# Controller.net
KiCad netlist of a schematic drawn in Altium Designer
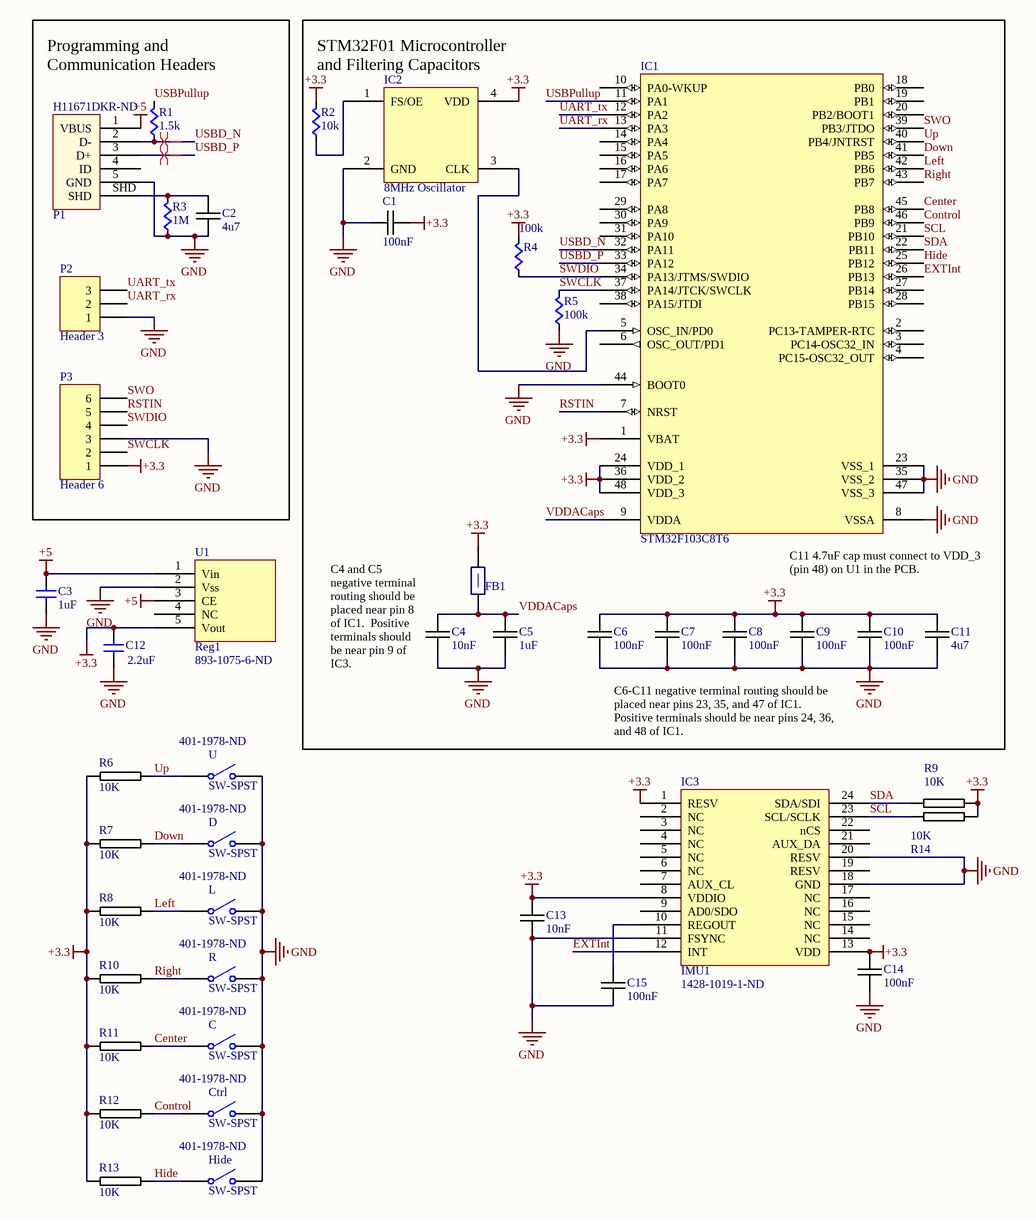
[diagram p0: Controller.SchDoc]

(export (version "E")
  (design (tool "Eeschema 10.0.6"))
  (components
    (comp (ref "C")
      (value "SW-SPST")
      (footprint "SPST C&K D6 Switch")
      (description "Single-Pole, Single-Throw Switch")
      (fields
        (field (name "SUPPLIER PART NUMBER 1") "401-1978-ND")
        (field (name "PUBLISHER") "Altium Limited")
      )
      (libsource (lib "Miscellaneous Devices") (part "SW-SPST"))
    )
    (comp (ref "C1")
      (value "100nF")
      (footprint "0603C-GENERIC")
      (description "CAP CER .10UF 25V X7R 10% 0603")
      (fields (field (name "MANUFACTURER") "TDK Corporation"))
      (libsource (lib "vh_altium_library") (part "0603C-100NF-25V-X7R-TDK"))
    )
    (comp (ref "C2")
      (value "4u7")
      (footprint "0603C-GENERIC")
      (description "CAPACITOR 0603 CERAMIC")
      (fields
        (field (name "MANUFACTURER PART NUMBER") "C1608X5R1A475K")
        (field (name "MANUFACTURER") "TDK Corporation")
      )
      (libsource (lib "vh_altium_library") (part "0603C-4U7-10V-X5R-TDK"))
    )
    (comp (ref "C3")
      (value "1uF")
      (footprint "CAPC0603")
      (fields (field (name "Comment") "Cap"))
      (libsource (lib "Passives") (part "Cap"))
    )
    (comp (ref "C4")
      (value "10nF")
      (footprint "0603C-GENERIC")
      (description "CAPACITOR 0603 CERAMIC")
      (fields
        (field (name "MANUFACTURER PART NUMBER") "GRM188R71H103KA01D")
        (field (name "MANUFACTURER") "Murata Electronics North America")
      )
      (libsource (lib "vh_altium_library") (part "0603C-10NF-50V-X7R-MUR"))
    )
    (comp (ref "C5")
      (value "1uF")
      (footprint "0603C-GENERIC")
      (description "CAPACITOR 0603 CERAMIC")
      (libsource (lib "vh_altium_library") (part "0603C-1UF-25V-X5R-SAM"))
    )
    (comp (ref "C6")
      (value "100nF")
      (footprint "0603C-GENERIC")
      (description "CAP CER 10000PF 50V X7R 10% 0603")
      (fields (field (name "TOLERANCE") "±10%"))
      (libsource (lib "vh_altium_library") (part "0603C-100NF-50V-X7R-TDK"))
    )
    (comp (ref "C7")
      (value "100nF")
      (footprint "0603C-GENERIC")
      (description "CAP CER 10000PF 50V X7R 10% 0603")
      (fields (field (name "TOLERANCE") "±10%"))
      (libsource (lib "vh_altium_library") (part "0603C-100NF-50V-X7R-TDK"))
    )
    (comp (ref "C8")
      (value "100nF")
      (footprint "0603C-GENERIC")
      (description "CAP CER 10000PF 50V X7R 10% 0603")
      (fields (field (name "TOLERANCE") "±10%"))
      (libsource (lib "vh_altium_library") (part "0603C-100NF-50V-X7R-TDK"))
    )
    (comp (ref "C9")
      (value "100nF")
      (footprint "0603C-GENERIC")
      (description "CAP CER 10000PF 50V X7R 10% 0603")
      (fields (field (name "TOLERANCE") "±10%"))
      (libsource (lib "vh_altium_library") (part "0603C-100NF-50V-X7R-TDK"))
    )
    (comp (ref "C10")
      (value "100nF")
      (footprint "0603C-GENERIC")
      (description "CAP CER 10000PF 50V X7R 10% 0603")
      (fields (field (name "TOLERANCE") "±10%"))
      (libsource (lib "vh_altium_library") (part "0603C-100NF-50V-X7R-TDK"))
    )
    (comp (ref "C11")
      (value "4u7")
      (footprint "0603C-GENERIC")
      (description "CAPACITOR 0603 CERAMIC")
      (fields
        (field (name "MANUFACTURER PART NUMBER") "C1608X5R1A475K")
        (field (name "MANUFACTURER") "TDK Corporation")
      )
      (libsource (lib "vh_altium_library") (part "0603C-4U7-10V-X5R-TDK"))
    )
    (comp (ref "C12")
      (value "2.2uF")
      (footprint "CAPC0603")
      (fields (field (name "Comment") "Cap"))
      (libsource (lib "Passives") (part "Cap"))
    )
    (comp (ref "C13")
      (value "10nF")
      (footprint "0603C-GENERIC")
      (description "CAPACITOR 0603 CERAMIC")
      (fields
        (field (name "MANUFACTURER PART NUMBER") "GRM188R71H103KA01D")
        (field (name "MANUFACTURER") "Murata Electronics North America")
      )
      (libsource (lib "vh_altium_library") (part "0603C-10NF-50V-X7R-MUR"))
    )
    (comp (ref "C14")
      (value "100nF")
      (footprint "0603C-GENERIC")
      (description "CAP CER .10UF 25V X7R 10% 0603")
      (fields (field (name "MANUFACTURER PART NUMBER") "C1608X7R1E104K"))
      (libsource (lib "vh_altium_library") (part "0603C-100NF-25V-X7R-TDK"))
    )
    (comp (ref "C15")
      (value "100nF")
      (footprint "0603C-GENERIC")
      (description "CAP CER .10UF 25V X7R 10% 0603")
      (fields (field (name "MANUFACTURER PART NUMBER") "C1608X7R1E104K"))
      (libsource (lib "vh_altium_library") (part "0603C-100NF-25V-X7R-TDK"))
    )
    (comp (ref "Ctrl")
      (value "SW-SPST")
      (footprint "SPST C&K D6 Switch")
      (description "Single-Pole, Single-Throw Switch")
      (fields
        (field (name "SUPPLIER PART NUMBER 1") "401-1978-ND")
        (field (name "PUBLISHER") "Altium Limited")
      )
      (libsource (lib "Miscellaneous Devices") (part "SW-SPST"))
    )
    (comp (ref "D")
      (value "SW-SPST")
      (footprint "SPST C&K D6 Switch")
      (description "Single-Pole, Single-Throw Switch")
      (fields
        (field (name "SUPPLIER PART NUMBER 1") "401-1978-ND")
        (field (name "PUBLISHER") "Altium Limited")
      )
      (libsource (lib "Miscellaneous Devices") (part "SW-SPST"))
    )
    (comp (ref "FB1")
      (value "FBead")
      (footprint "RES0603")
      (description "Ferrite Bead")
      (libsource (lib "Passives") (part "FBead"))
    )
    (comp (ref "Hide")
      (value "SW-SPST")
      (footprint "SPST C&K D6 Switch")
      (description "Single-Pole, Single-Throw Switch")
      (fields
        (field (name "SUPPLIER PART NUMBER 1") "401-1978-ND")
        (field (name "PUBLISHER") "Altium Limited")
      )
      (libsource (lib "Miscellaneous Devices") (part "SW-SPST"))
    )
    (comp (ref "IC1")
      (value "STM32F103C8T6")
      (footprint "LQFP48_N")
      (description "STM32 ARM-based 32-bit MCU with 64 Kbytes Flash, 48-pin LQFP, Industrial Temperature")
      (fields (field (name "PUBLISHER") "Altium Limited"))
      (libsource (lib "ST Microcontroller 32-Bit STM32") (part "STM32F103C8T6"))
    )
    (comp (ref "IC2")
      (value "8MHz Oscillator")
      (footprint "3.2 x 5 mm 4-pin DFN")
      (description "Oscillator")
      (libsource (lib "CustomLib") (part "Si501 Oscillator"))
    )
    (comp (ref "IC3")
      (value "IMU1")
      (footprint "QFN50P300X300X100-24N")
      (description "9-DOF IMU")
      (fields (field (name "SUPPLIER PART NUMBER 1") "1428-1019-1-ND"))
      (libsource (lib "CustomLib") (part "MPU9250"))
    )
    (comp (ref "L")
      (value "SW-SPST")
      (footprint "SPST C&K D6 Switch")
      (description "Single-Pole, Single-Throw Switch")
      (fields
        (field (name "SUPPLIER PART NUMBER 1") "401-1978-ND")
        (field (name "PUBLISHER") "Altium Limited")
      )
      (libsource (lib "Miscellaneous Devices") (part "SW-SPST"))
    )
    (comp (ref "P1")
      (value "UX60SC-MB-5ST")
      (footprint "UX60SC-MB-5ST")
      (description "USB Mini B Metal Shield SMT")
      (fields (field (name "SUPPLIER PART NUMBER 1") "H11671DKR-ND"))
      (libsource (lib "Connectors") (part "UX60SC-MB-5ST"))
    )
    (comp (ref "P2")
      (value "Header 3")
      (footprint "HDR1X3")
      (description "Header, 3-Pin")
      (fields (field (name "PUBLISHER") "Altium Limited"))
      (libsource (lib "Miscellaneous Connectors") (part "Header 3"))
    )
    (comp (ref "P3")
      (value "Header 6")
      (footprint "HDR1X6")
      (description "Header, 6-Pin")
      (fields (field (name "PUBLISHER") "Altium Limited"))
      (libsource (lib "Miscellaneous Connectors") (part "Header 6"))
    )
    (comp (ref "R")
      (value "SW-SPST")
      (footprint "SPST C&K D6 Switch")
      (description "Single-Pole, Single-Throw Switch")
      (fields
        (field (name "SUPPLIER PART NUMBER 1") "401-1978-ND")
        (field (name "PUBLISHER") "Altium Limited")
      )
      (libsource (lib "Miscellaneous Devices") (part "SW-SPST"))
    )
    (comp (ref "R1")
      (value "1.5k")
      (footprint "RES0603")
      (fields (field (name "Comment") "Res"))
      (libsource (lib "Passives") (part "Res"))
    )
    (comp (ref "R2")
      (value "10k")
      (footprint "RES0603")
      (fields (field (name "Comment") "Res"))
      (libsource (lib "Passives") (part "Res"))
    )
    (comp (ref "R3")
      (value "1M")
      (footprint "RES0603")
      (fields (field (name "Comment") "Res"))
      (libsource (lib "Passives") (part "Res"))
    )
    (comp (ref "R4")
      (value "100k")
      (footprint "RES0603")
      (fields (field (name "Comment") "Res"))
      (libsource (lib "Passives") (part "Res"))
    )
    (comp (ref "R5")
      (value "100k")
      (footprint "RES0603")
      (fields (field (name "Comment") "Res"))
      (libsource (lib "Passives") (part "Res"))
    )
    (comp (ref "R6")
      (value "10K")
      (footprint "0603R-10K")
      (description "GENERIC RESISTOR 0603")
      (fields (field (name "MANUFACTURER") "Stackpole Electronics Inc") (field (name "TOLERANCE") "±1%"))
      (libsource (lib "vh_altium_library") (part "0603R-10K"))
    )
    (comp (ref "R7")
      (value "10K")
      (footprint "0603R-10K")
      (description "GENERIC RESISTOR 0603")
      (fields (field (name "MANUFACTURER") "Stackpole Electronics Inc") (field (name "TOLERANCE") "±1%"))
      (libsource (lib "vh_altium_library") (part "0603R-10K"))
    )
    (comp (ref "R8")
      (value "10K")
      (footprint "0603R-10K")
      (description "GENERIC RESISTOR 0603")
      (fields (field (name "MANUFACTURER") "Stackpole Electronics Inc") (field (name "TOLERANCE") "±1%"))
      (libsource (lib "vh_altium_library") (part "0603R-10K"))
    )
    (comp (ref "R9")
      (value "10K")
      (footprint "0603R-10K")
      (description "GENERIC RESISTOR 0603")
      (fields (field (name "MANUFACTURER") "Stackpole Electronics Inc") (field (name "TOLERANCE") "±1%"))
      (libsource (lib "vh_altium_library") (part "0603R-10K"))
    )
    (comp (ref "R10")
      (value "10K")
      (footprint "0603R-10K")
      (description "GENERIC RESISTOR 0603")
      (fields (field (name "MANUFACTURER") "Stackpole Electronics Inc") (field (name "TOLERANCE") "±1%"))
      (libsource (lib "vh_altium_library") (part "0603R-10K"))
    )
    (comp (ref "R11")
      (value "10K")
      (footprint "0603R-10K")
      (description "GENERIC RESISTOR 0603")
      (fields (field (name "MANUFACTURER") "Stackpole Electronics Inc") (field (name "TOLERANCE") "±1%"))
      (libsource (lib "vh_altium_library") (part "0603R-10K"))
    )
    (comp (ref "R12")
      (value "10K")
      (footprint "0603R-10K")
      (description "GENERIC RESISTOR 0603")
      (fields (field (name "MANUFACTURER") "Stackpole Electronics Inc") (field (name "TOLERANCE") "±1%"))
      (libsource (lib "vh_altium_library") (part "0603R-10K"))
    )
    (comp (ref "R13")
      (value "10K")
      (footprint "0603R-10K")
      (description "GENERIC RESISTOR 0603")
      (fields (field (name "MANUFACTURER") "Stackpole Electronics Inc") (field (name "TOLERANCE") "±1%"))
      (libsource (lib "vh_altium_library") (part "0603R-10K"))
    )
    (comp (ref "R14")
      (value "10K")
      (footprint "0603R-10K")
      (description "GENERIC RESISTOR 0603")
      (fields (field (name "MANUFACTURER") "Stackpole Electronics Inc") (field (name "TOLERANCE") "±1%"))
      (libsource (lib "vh_altium_library") (part "0603R-10K"))
    )
    (comp (ref "U")
      (value "SW-SPST")
      (footprint "SPST C&K D6 Switch")
      (description "Single-Pole, Single-Throw Switch")
      (fields
        (field (name "SUPPLIER PART NUMBER 1") "401-1978-ND")
        (field (name "PUBLISHER") "Altium Limited")
      )
      (libsource (lib "Miscellaneous Devices") (part "SW-SPST"))
    )
    (comp (ref "U1")
      (value "Reg1")
      (footprint "SOT-25")
      (description "Voltage Regulator")
      (fields (field (name "SUPPLIER PART NUMBER 1") "893-1075-6-ND"))
      (libsource (lib "CustomLib") (part "3VRegulator"))
    )
  )
  (nets
    (net (code "1") (name "+3.3") (class "Default")
      (node (ref "C1") (pin "2") (pintype "passive"))
      (node (ref "C10") (pin "1") (pintype "passive"))
      (node (ref "C11") (pin "1") (pintype "passive"))
      (node (ref "C12") (pin "1") (pinfunction "A_1") (pintype "passive"))
      (node (ref "C13") (pin "2") (pintype "passive"))
      (node (ref "C14") (pin "1") (pintype "passive"))
      (node (ref "C6") (pin "1") (pintype "passive"))
      (node (ref "C7") (pin "1") (pintype "passive"))
      (node (ref "C8") (pin "1") (pintype "passive"))
      (node (ref "C9") (pin "1") (pintype "passive"))
      (node (ref "FB1") (pin "2") (pinfunction "B_2") (pintype "passive"))
      (node (ref "IC1") (pin "1") (pinfunction "VBAT_1") (pintype "power_in"))
      (node (ref "IC1") (pin "24") (pinfunction "VDD_1_24") (pintype "power_in"))
      (node (ref "IC1") (pin "36") (pinfunction "VDD_2_36") (pintype "power_in"))
      (node (ref "IC1") (pin "48") (pinfunction "VDD_3_48") (pintype "power_in"))
      (node (ref "IC2") (pin "4") (pinfunction "VDD_4") (pintype "passive"))
      (node (ref "IC3") (pin "1") (pinfunction "RESV_1") (pintype "passive"))
      (node (ref "IC3") (pin "13") (pinfunction "VDD_13") (pintype "passive"))
      (node (ref "IC3") (pin "8") (pinfunction "VDDIO_8") (pintype "passive"))
      (node (ref "P3") (pin "1") (pinfunction "1_1") (pintype "passive"))
      (node (ref "R10") (pin "1") (pintype "passive"))
      (node (ref "R11") (pin "1") (pintype "passive"))
      (node (ref "R12") (pin "1") (pintype "passive"))
      (node (ref "R13") (pin "1") (pintype "passive"))
      (node (ref "R14") (pin "2") (pintype "passive"))
      (node (ref "R2") (pin "1") (pinfunction "A_1") (pintype "passive"))
      (node (ref "R4") (pin "1") (pinfunction "A_1") (pintype "passive"))
      (node (ref "R6") (pin "1") (pintype "passive"))
      (node (ref "R7") (pin "1") (pintype "passive"))
      (node (ref "R8") (pin "1") (pintype "passive"))
      (node (ref "R9") (pin "2") (pintype "passive"))
      (node (ref "U1") (pin "5") (pinfunction "Vout_5") (pintype "passive"))
    )
    (net (code "2") (name "+5") (class "Default")
      (node (ref "C3") (pin "1") (pinfunction "A_1") (pintype "passive"))
      (node (ref "P1") (pin "1") (pinfunction "VBUS_1") (pintype "passive"))
      (node (ref "U1") (pin "1") (pinfunction "Vin_1") (pintype "passive"))
      (node (ref "U1") (pin "3") (pinfunction "CE_3") (pintype "passive"))
    )
    (net (code "3") (name "/Center") (class "Default")
      (node (ref "C") (pin "1") (pinfunction "COMMON_1") (pintype "passive"))
      (node (ref "IC1") (pin "45") (pinfunction "PB8_45") (pintype "bidirectional"))
      (node (ref "R11") (pin "2") (pintype "passive"))
    )
    (net (code "4") (name "/Control") (class "Default")
      (node (ref "Ctrl") (pin "1") (pinfunction "COMMON_1") (pintype "passive"))
      (node (ref "IC1") (pin "46") (pinfunction "PB9_46") (pintype "bidirectional"))
      (node (ref "R12") (pin "2") (pintype "passive"))
    )
    (net (code "5") (name "/Down") (class "Default")
      (node (ref "D") (pin "1") (pinfunction "COMMON_1") (pintype "passive"))
      (node (ref "IC1") (pin "41") (pinfunction "PB5_41") (pintype "bidirectional"))
      (node (ref "R7") (pin "2") (pintype "passive"))
    )
    (net (code "6") (name "/EXTInt") (class "Default")
      (node (ref "IC1") (pin "26") (pinfunction "PB13_26") (pintype "bidirectional"))
      (node (ref "IC3") (pin "12") (pinfunction "INT_12") (pintype "passive"))
    )
    (net (code "7") (name "/Hide") (class "Default")
      (node (ref "Hide") (pin "1") (pinfunction "COMMON_1") (pintype "passive"))
      (node (ref "IC1") (pin "25") (pinfunction "PB12_25") (pintype "bidirectional"))
      (node (ref "R13") (pin "2") (pintype "passive"))
    )
    (net (code "8") (name "/Left") (class "Default")
      (node (ref "IC1") (pin "42") (pinfunction "PB6_42") (pintype "bidirectional"))
      (node (ref "L") (pin "1") (pinfunction "COMMON_1") (pintype "passive"))
      (node (ref "R8") (pin "2") (pintype "passive"))
    )
    (net (code "9") (name "/RSTIN") (class "Default")
      (node (ref "IC1") (pin "7") (pinfunction "NRST_7") (pintype "bidirectional"))
      (node (ref "P3") (pin "5") (pinfunction "5_5") (pintype "passive"))
    )
    (net (code "10") (name "/Right") (class "Default")
      (node (ref "IC1") (pin "43") (pinfunction "PB7_43") (pintype "bidirectional"))
      (node (ref "R") (pin "1") (pinfunction "COMMON_1") (pintype "passive"))
      (node (ref "R10") (pin "2") (pintype "passive"))
    )
    (net (code "11") (name "/SCL") (class "Default")
      (node (ref "IC1") (pin "21") (pinfunction "PB10_21") (pintype "bidirectional"))
      (node (ref "IC3") (pin "23") (pinfunction "SCL/SCLK_23") (pintype "passive"))
      (node (ref "R14") (pin "1") (pintype "passive"))
    )
    (net (code "12") (name "/SDA") (class "Default")
      (node (ref "IC1") (pin "22") (pinfunction "PB11_22") (pintype "bidirectional"))
      (node (ref "IC3") (pin "24") (pinfunction "SDA/SDI_24") (pintype "passive"))
      (node (ref "R9") (pin "1") (pintype "passive"))
    )
    (net (code "13") (name "/SWCLK") (class "Default")
      (node (ref "IC1") (pin "37") (pinfunction "PA14/JTCK/SWCLK_37") (pintype "bidirectional"))
      (node (ref "P3") (pin "2") (pinfunction "2_2") (pintype "passive"))
      (node (ref "R5") (pin "1") (pinfunction "A_1") (pintype "passive"))
    )
    (net (code "14") (name "/SWDIO") (class "Default")
      (node (ref "IC1") (pin "34") (pinfunction "PA13/JTMS/SWDIO_34") (pintype "bidirectional"))
      (node (ref "P3") (pin "4") (pinfunction "4_4") (pintype "passive"))
      (node (ref "R4") (pin "2") (pinfunction "B_2") (pintype "passive"))
    )
    (net (code "15") (name "/SWO") (class "Default")
      (node (ref "IC1") (pin "39") (pinfunction "PB3/JTDO_39") (pintype "bidirectional"))
      (node (ref "P3") (pin "6") (pinfunction "6_6") (pintype "passive"))
    )
    (net (code "16") (name "/UART_rx") (class "Default")
      (node (ref "IC1") (pin "13") (pinfunction "PA3_13") (pintype "bidirectional"))
      (node (ref "P2") (pin "2") (pinfunction "2_2") (pintype "passive"))
    )
    (net (code "17") (name "/UART_tx") (class "Default")
      (node (ref "IC1") (pin "12") (pinfunction "PA2_12") (pintype "bidirectional"))
      (node (ref "P2") (pin "3") (pinfunction "3_3") (pintype "passive"))
    )
    (net (code "18") (name "/USBD_N") (class "Default")
      (node (ref "IC1") (pin "32") (pinfunction "PA11_32") (pintype "bidirectional"))
      (node (ref "P1") (pin "2") (pinfunction "D-_2") (pintype "passive"))
      (node (ref "R1") (pin "2") (pinfunction "B_2") (pintype "passive"))
    )
    (net (code "19") (name "/USBD_P") (class "Default")
      (node (ref "IC1") (pin "33") (pinfunction "PA12_33") (pintype "bidirectional"))
      (node (ref "P1") (pin "3") (pinfunction "D+_3") (pintype "passive"))
    )
    (net (code "20") (name "/USBPullup") (class "Default")
      (node (ref "IC1") (pin "11") (pinfunction "PA1_11") (pintype "bidirectional"))
      (node (ref "R1") (pin "1") (pinfunction "A_1") (pintype "passive"))
    )
    (net (code "21") (name "/Up") (class "Default")
      (node (ref "IC1") (pin "40") (pinfunction "PB4/JNTRST_40") (pintype "bidirectional"))
      (node (ref "R6") (pin "2") (pintype "passive"))
      (node (ref "U") (pin "1") (pinfunction "COMMON_1") (pintype "passive"))
    )
    (net (code "22") (name "/VDDACaps") (class "Default")
      (node (ref "C4") (pin "1") (pintype "passive"))
      (node (ref "C5") (pin "1") (pintype "passive"))
      (node (ref "FB1") (pin "1") (pinfunction "A_1") (pintype "passive"))
      (node (ref "IC1") (pin "9") (pinfunction "VDDA_9") (pintype "power_in"))
    )
    (net (code "23") (name "GND") (class "Default")
      (node (ref "C") (pin "2") (pinfunction "NO_2") (pintype "passive"))
      (node (ref "C1") (pin "1") (pintype "passive"))
      (node (ref "C10") (pin "2") (pintype "passive"))
      (node (ref "C11") (pin "2") (pintype "passive"))
      (node (ref "C12") (pin "2") (pinfunction "B_2") (pintype "passive"))
      (node (ref "C13") (pin "1") (pintype "passive"))
      (node (ref "C14") (pin "2") (pintype "passive"))
      (node (ref "C15") (pin "2") (pintype "passive"))
      (node (ref "C2") (pin "2") (pintype "passive"))
      (node (ref "C3") (pin "2") (pinfunction "B_2") (pintype "passive"))
      (node (ref "C4") (pin "2") (pintype "passive"))
      (node (ref "C5") (pin "2") (pintype "passive"))
      (node (ref "C6") (pin "2") (pintype "passive"))
      (node (ref "C7") (pin "2") (pintype "passive"))
      (node (ref "C8") (pin "2") (pintype "passive"))
      (node (ref "C9") (pin "2") (pintype "passive"))
      (node (ref "Ctrl") (pin "2") (pinfunction "NO_2") (pintype "passive"))
      (node (ref "D") (pin "2") (pinfunction "NO_2") (pintype "passive"))
      (node (ref "Hide") (pin "2") (pinfunction "NO_2") (pintype "passive"))
      (node (ref "IC1") (pin "23") (pinfunction "VSS_1_23") (pintype "power_in"))
      (node (ref "IC1") (pin "35") (pinfunction "VSS_2_35") (pintype "power_in"))
      (node (ref "IC1") (pin "44") (pinfunction "BOOT0_44") (pintype "input"))
      (node (ref "IC1") (pin "47") (pinfunction "VSS_3_47") (pintype "power_in"))
      (node (ref "IC1") (pin "8") (pinfunction "VSSA_8") (pintype "power_in"))
      (node (ref "IC2") (pin "2") (pinfunction "GND_2") (pintype "passive"))
      (node (ref "IC3") (pin "11") (pinfunction "FSYNC_11") (pintype "passive"))
      (node (ref "IC3") (pin "18") (pinfunction "GND_18") (pintype "passive"))
      (node (ref "IC3") (pin "20") (pinfunction "RESV_20") (pintype "passive"))
      (node (ref "L") (pin "2") (pinfunction "NO_2") (pintype "passive"))
      (node (ref "P1") (pin "5") (pinfunction "GND_5") (pintype "passive"))
      (node (ref "P2") (pin "1") (pinfunction "1_1") (pintype "passive"))
      (node (ref "P3") (pin "3") (pinfunction "3_3") (pintype "passive"))
      (node (ref "R") (pin "2") (pinfunction "NO_2") (pintype "passive"))
      (node (ref "R3") (pin "2") (pinfunction "B_2") (pintype "passive"))
      (node (ref "R5") (pin "2") (pinfunction "B_2") (pintype "passive"))
      (node (ref "U") (pin "2") (pinfunction "NO_2") (pintype "passive"))
      (node (ref "U1") (pin "2") (pinfunction "Vss_2") (pintype "passive"))
    )
    (net (code "24") (name "Net-(IC1-OSC_IN{slash}PD0)") (class "Default")
      (node (ref "IC1") (pin "5") (pinfunction "OSC_IN/PD0_5") (pintype "input"))
      (node (ref "IC2") (pin "3") (pinfunction "CLK_3") (pintype "passive"))
    )
    (net (code "25") (name "Net-(IC2-FS{slash}OE)") (class "Default")
      (node (ref "IC2") (pin "1") (pinfunction "FS/OE_1") (pintype "passive"))
      (node (ref "R2") (pin "2") (pinfunction "B_2") (pintype "passive"))
    )
    (net (code "26") (name "Net-(IC3-REGOUT)") (class "Default")
      (node (ref "C15") (pin "1") (pintype "passive"))
      (node (ref "IC3") (pin "10") (pinfunction "REGOUT_10") (pintype "passive"))
    )
    (net (code "27") (name "Net-(R3-A)") (class "Default")
      (node (ref "C2") (pin "1") (pintype "passive"))
      (node (ref "P1") (pin "SHD") (pinfunction "SHD_SHD") (pintype "passive"))
      (node (ref "R3") (pin "1") (pinfunction "A_1") (pintype "passive"))
    )
    (net (code "28") (name "unconnected-(IC1-OSC_OUT{slash}PD1-Pad6)") (class "Default")
      (node (ref "IC1") (pin "6") (pinfunction "OSC_OUT/PD1_6") (pintype "output"))
    )
    (net (code "29") (name "unconnected-(IC1-PA0-WKUP-Pad10)") (class "Default")
      (node (ref "IC1") (pin "10") (pinfunction "PA0-WKUP_10") (pintype "bidirectional"))
    )
    (net (code "30") (name "unconnected-(IC1-PA4-Pad14)") (class "Default")
      (node (ref "IC1") (pin "14") (pinfunction "PA4_14") (pintype "bidirectional"))
    )
    (net (code "31") (name "unconnected-(IC1-PA5-Pad15)") (class "Default")
      (node (ref "IC1") (pin "15") (pinfunction "PA5_15") (pintype "bidirectional"))
    )
    (net (code "32") (name "unconnected-(IC1-PA6-Pad16)") (class "Default")
      (node (ref "IC1") (pin "16") (pinfunction "PA6_16") (pintype "bidirectional"))
    )
    (net (code "33") (name "unconnected-(IC1-PA7-Pad17)") (class "Default")
      (node (ref "IC1") (pin "17") (pinfunction "PA7_17") (pintype "bidirectional"))
    )
    (net (code "34") (name "unconnected-(IC1-PA8-Pad29)") (class "Default")
      (node (ref "IC1") (pin "29") (pinfunction "PA8_29") (pintype "bidirectional"))
    )
    (net (code "35") (name "unconnected-(IC1-PA9-Pad30)") (class "Default")
      (node (ref "IC1") (pin "30") (pinfunction "PA9_30") (pintype "bidirectional"))
    )
    (net (code "36") (name "unconnected-(IC1-PA10-Pad31)") (class "Default")
      (node (ref "IC1") (pin "31") (pinfunction "PA10_31") (pintype "bidirectional"))
    )
    (net (code "37") (name "unconnected-(IC1-PA15{slash}JTDI-Pad38)") (class "Default")
      (node (ref "IC1") (pin "38") (pinfunction "PA15/JTDI_38") (pintype "bidirectional"))
    )
    (net (code "38") (name "unconnected-(IC1-PB0-Pad18)") (class "Default")
      (node (ref "IC1") (pin "18") (pinfunction "PB0_18") (pintype "bidirectional"))
    )
    (net (code "39") (name "unconnected-(IC1-PB1-Pad19)") (class "Default")
      (node (ref "IC1") (pin "19") (pinfunction "PB1_19") (pintype "bidirectional"))
    )
    (net (code "40") (name "unconnected-(IC1-PB2{slash}BOOT1-Pad20)") (class "Default")
      (node (ref "IC1") (pin "20") (pinfunction "PB2/BOOT1_20") (pintype "bidirectional"))
    )
    (net (code "41") (name "unconnected-(IC1-PB14-Pad27)") (class "Default")
      (node (ref "IC1") (pin "27") (pinfunction "PB14_27") (pintype "bidirectional"))
    )
    (net (code "42") (name "unconnected-(IC1-PB15-Pad28)") (class "Default")
      (node (ref "IC1") (pin "28") (pinfunction "PB15_28") (pintype "bidirectional"))
    )
    (net (code "43") (name "unconnected-(IC1-PC13-TAMPER-RTC-Pad2)") (class "Default")
      (node (ref "IC1") (pin "2") (pinfunction "PC13-TAMPER-RTC_2") (pintype "bidirectional"))
    )
    (net (code "44") (name "unconnected-(IC1-PC14-OSC32_IN-Pad3)") (class "Default")
      (node (ref "IC1") (pin "3") (pinfunction "PC14-OSC32_IN_3") (pintype "bidirectional"))
    )
    (net (code "45") (name "unconnected-(IC1-PC15-OSC32_OUT-Pad4)") (class "Default")
      (node (ref "IC1") (pin "4") (pinfunction "PC15-OSC32_OUT_4") (pintype "bidirectional"))
    )
    (net (code "46") (name "unconnected-(IC3-AD0{slash}SDO-Pad9)") (class "Default")
      (node (ref "IC3") (pin "9") (pinfunction "AD0/SDO_9") (pintype "passive"))
    )
    (net (code "47") (name "unconnected-(IC3-AUX_CL-Pad7)") (class "Default")
      (node (ref "IC3") (pin "7") (pinfunction "AUX_CL_7") (pintype "passive"))
    )
    (net (code "48") (name "unconnected-(IC3-AUX_DA-Pad21)") (class "Default")
      (node (ref "IC3") (pin "21") (pinfunction "AUX_DA_21") (pintype "passive"))
    )
    (net (code "49") (name "unconnected-(IC3-NC-Pad2)") (class "Default")
      (node (ref "IC3") (pin "2") (pinfunction "NC_2") (pintype "passive"))
    )
    (net (code "50") (name "unconnected-(IC3-NC-Pad3)") (class "Default")
      (node (ref "IC3") (pin "3") (pinfunction "NC_3") (pintype "passive"))
    )
    (net (code "51") (name "unconnected-(IC3-NC-Pad4)") (class "Default")
      (node (ref "IC3") (pin "4") (pinfunction "NC_4") (pintype "passive"))
    )
    (net (code "52") (name "unconnected-(IC3-NC-Pad5)") (class "Default")
      (node (ref "IC3") (pin "5") (pinfunction "NC_5") (pintype "passive"))
    )
    (net (code "53") (name "unconnected-(IC3-NC-Pad6)") (class "Default")
      (node (ref "IC3") (pin "6") (pinfunction "NC_6") (pintype "passive"))
    )
    (net (code "54") (name "unconnected-(IC3-NC-Pad14)") (class "Default")
      (node (ref "IC3") (pin "14") (pinfunction "NC_14") (pintype "passive"))
    )
    (net (code "55") (name "unconnected-(IC3-NC-Pad15)") (class "Default")
      (node (ref "IC3") (pin "15") (pinfunction "NC_15") (pintype "passive"))
    )
    (net (code "56") (name "unconnected-(IC3-NC-Pad16)") (class "Default")
      (node (ref "IC3") (pin "16") (pinfunction "NC_16") (pintype "passive"))
    )
    (net (code "57") (name "unconnected-(IC3-NC-Pad17)") (class "Default")
      (node (ref "IC3") (pin "17") (pinfunction "NC_17") (pintype "passive"))
    )
    (net (code "58") (name "unconnected-(IC3-RESV-Pad19)") (class "Default")
      (node (ref "IC3") (pin "19") (pinfunction "RESV_19") (pintype "passive"))
    )
    (net (code "59") (name "unconnected-(IC3-nCS-Pad22)") (class "Default")
      (node (ref "IC3") (pin "22") (pinfunction "nCS_22") (pintype "passive"))
    )
    (net (code "60") (name "unconnected-(P1-ID-Pad4)") (class "Default")
      (node (ref "P1") (pin "4") (pinfunction "ID_4") (pintype "passive"))
    )
    (net (code "61") (name "unconnected-(U1-NC-Pad4)") (class "Default")
      (node (ref "U1") (pin "4") (pinfunction "NC_4") (pintype "passive"))
    )
  )
)
